# ART-Pi_LCD_Camera.net
KiCad netlist of a schematic drawn in Altium Designer
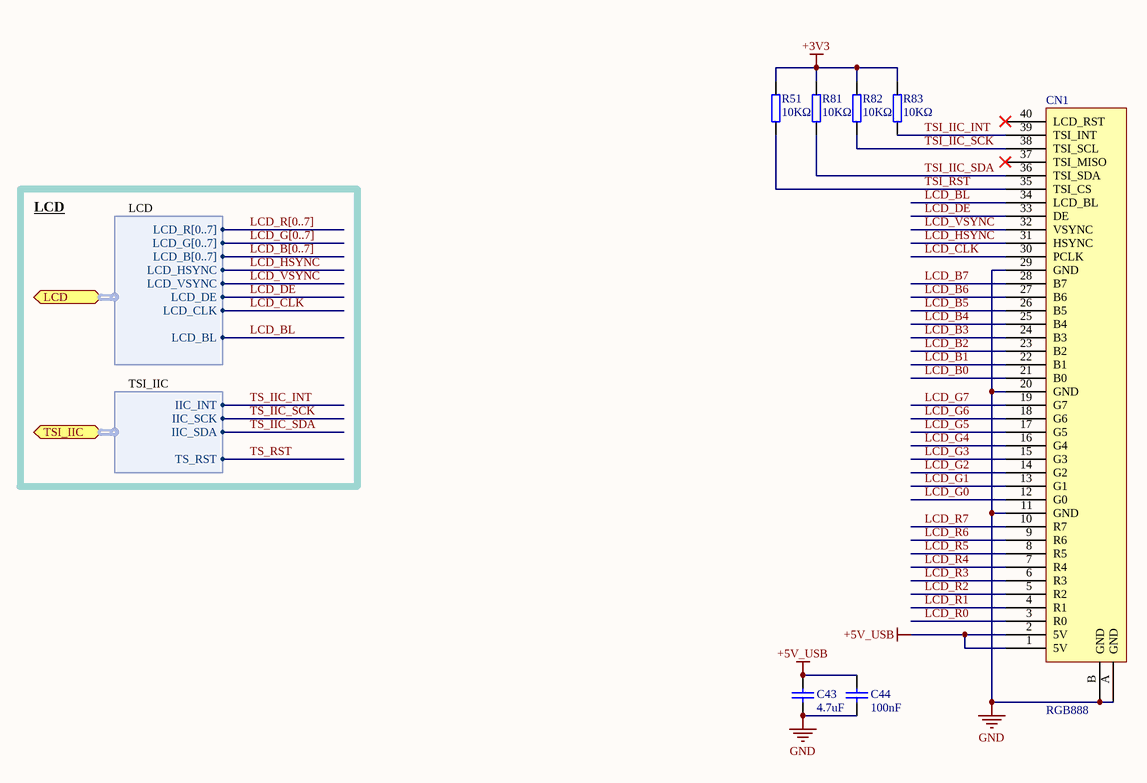
[diagram p0: ART-Pi_LCD&Camera.SchDoc]

(export (version "E")
  (design (tool "Eeschema 10.0.6"))
  (components
    (comp (ref "C43")
      (value "4.7uF")
      (footprint "0402_C")
      (description "Capacitor")
      (fields (field (name "PUBLISHER") "Altium Limited"))
      (libsource (lib "ART-Pi_STM32H750_COPY") (part "Cap"))
    )
    (comp (ref "C44")
      (value "100nF")
      (footprint "0402_C")
      (description "Capacitor")
      (fields (field (name "PUBLISHER") "Altium Limited"))
      (libsource (lib "ART-Pi_STM32H750_COPY") (part "Cap"))
    )
    (comp (ref "CN1")
      (value "RGB888")
      (footprint "FPC-TOP40")
      (description "FPC-40P-0.5mm")
      (libsource (lib "ART-Pi_STM32H750_COPY") (part "FPC-40"))
    )
    (comp (ref "R51")
      (value "10KΩ")
      (footprint "0402_R")
      (description "Resister")
      (libsource (lib "ART-Pi_STM32H750_COPY") (part "Res"))
    )
    (comp (ref "R81")
      (value "10KΩ")
      (footprint "0402_R")
      (description "Resister")
      (libsource (lib "ART-Pi_STM32H750_COPY") (part "Res"))
    )
    (comp (ref "R82")
      (value "10KΩ")
      (footprint "0402_R")
      (description "Resister")
      (libsource (lib "ART-Pi_STM32H750_COPY") (part "Res"))
    )
    (comp (ref "R83")
      (value "10KΩ")
      (footprint "0402_R")
      (description "Resister")
      (libsource (lib "ART-Pi_STM32H750_COPY") (part "Res"))
    )
  )
  (nets
    (net (code "2") (name "+3V3") (class "Default")
      (node (ref "R51") (pin "1") (pinfunction "1_1") (pintype "passive"))
      (node (ref "R81") (pin "1") (pinfunction "1_1") (pintype "passive"))
      (node (ref "R82") (pin "1") (pinfunction "1_1") (pintype "passive"))
      (node (ref "R83") (pin "1") (pinfunction "1_1") (pintype "passive"))
    )
    (net (code "3") (name "+5V_USB") (class "Default")
      (node (ref "C43") (pin "2") (pinfunction "2_2") (pintype "passive"))
      (node (ref "C44") (pin "2") (pinfunction "2_2") (pintype "passive"))
      (node (ref "CN1") (pin "1") (pinfunction "5V_1") (pintype "passive"))
      (node (ref "CN1") (pin "2") (pinfunction "5V_2") (pintype "passive"))
    )
    (net (code "4") (name "/LCD_B0") (class "Default")
      (node (ref "CN1") (pin "21") (pinfunction "B0_21") (pintype "passive"))
    )
    (net (code "5") (name "/LCD_B1") (class "Default")
      (node (ref "CN1") (pin "22") (pinfunction "B1_22") (pintype "passive"))
    )
    (net (code "6") (name "/LCD_B2") (class "Default")
      (node (ref "CN1") (pin "23") (pinfunction "B2_23") (pintype "passive"))
    )
    (net (code "7") (name "/LCD_B3") (class "Default")
      (node (ref "CN1") (pin "24") (pinfunction "B3_24") (pintype "passive"))
    )
    (net (code "8") (name "/LCD_B4") (class "Default")
      (node (ref "CN1") (pin "25") (pinfunction "B4_25") (pintype "passive"))
    )
    (net (code "9") (name "/LCD_B5") (class "Default")
      (node (ref "CN1") (pin "26") (pinfunction "B5_26") (pintype "passive"))
    )
    (net (code "10") (name "/LCD_B6") (class "Default")
      (node (ref "CN1") (pin "27") (pinfunction "B6_27") (pintype "passive"))
    )
    (net (code "11") (name "/LCD_B7") (class "Default")
      (node (ref "CN1") (pin "28") (pinfunction "B7_28") (pintype "passive"))
    )
    (net (code "12") (name "/LCD_BL") (class "Default")
      (node (ref "CN1") (pin "34") (pinfunction "LCD_BL_34") (pintype "passive"))
    )
    (net (code "14") (name "/LCD_CLK") (class "Default")
      (node (ref "CN1") (pin "30") (pinfunction "PCLK_30") (pintype "passive"))
    )
    (net (code "15") (name "/LCD_DE") (class "Default")
      (node (ref "CN1") (pin "33") (pinfunction "DE_33") (pintype "passive"))
    )
    (net (code "16") (name "/LCD_G0") (class "Default")
      (node (ref "CN1") (pin "12") (pinfunction "G0_12") (pintype "passive"))
    )
    (net (code "17") (name "/LCD_G1") (class "Default")
      (node (ref "CN1") (pin "13") (pinfunction "G1_13") (pintype "passive"))
    )
    (net (code "18") (name "/LCD_G2") (class "Default")
      (node (ref "CN1") (pin "14") (pinfunction "G2_14") (pintype "passive"))
    )
    (net (code "19") (name "/LCD_G3") (class "Default")
      (node (ref "CN1") (pin "15") (pinfunction "G3_15") (pintype "passive"))
    )
    (net (code "20") (name "/LCD_G4") (class "Default")
      (node (ref "CN1") (pin "16") (pinfunction "G4_16") (pintype "passive"))
    )
    (net (code "21") (name "/LCD_G5") (class "Default")
      (node (ref "CN1") (pin "17") (pinfunction "G5_17") (pintype "passive"))
    )
    (net (code "22") (name "/LCD_G6") (class "Default")
      (node (ref "CN1") (pin "18") (pinfunction "G6_18") (pintype "passive"))
    )
    (net (code "23") (name "/LCD_G7") (class "Default")
      (node (ref "CN1") (pin "19") (pinfunction "G7_19") (pintype "passive"))
    )
    (net (code "25") (name "/LCD_HSYNC") (class "Default")
      (node (ref "CN1") (pin "31") (pinfunction "HSYNC_31") (pintype "passive"))
    )
    (net (code "26") (name "/LCD_R0") (class "Default")
      (node (ref "CN1") (pin "3") (pinfunction "R0_3") (pintype "passive"))
    )
    (net (code "27") (name "/LCD_R1") (class "Default")
      (node (ref "CN1") (pin "4") (pinfunction "R1_4") (pintype "passive"))
    )
    (net (code "28") (name "/LCD_R2") (class "Default")
      (node (ref "CN1") (pin "5") (pinfunction "R2_5") (pintype "passive"))
    )
    (net (code "29") (name "/LCD_R3") (class "Default")
      (node (ref "CN1") (pin "6") (pinfunction "R3_6") (pintype "passive"))
    )
    (net (code "30") (name "/LCD_R4") (class "Default")
      (node (ref "CN1") (pin "7") (pinfunction "R4_7") (pintype "passive"))
    )
    (net (code "31") (name "/LCD_R5") (class "Default")
      (node (ref "CN1") (pin "8") (pinfunction "R5_8") (pintype "passive"))
    )
    (net (code "32") (name "/LCD_R6") (class "Default")
      (node (ref "CN1") (pin "9") (pinfunction "R6_9") (pintype "passive"))
    )
    (net (code "33") (name "/LCD_R7") (class "Default")
      (node (ref "CN1") (pin "10") (pinfunction "R7_10") (pintype "passive"))
    )
    (net (code "35") (name "/LCD_VSYNC") (class "Default")
      (node (ref "CN1") (pin "32") (pinfunction "VSYNC_32") (pintype "passive"))
    )
    (net (code "36") (name "/TSI_IIC_INT") (class "Default")
      (node (ref "CN1") (pin "39") (pinfunction "TSI_INT_39") (pintype "passive"))
      (node (ref "R83") (pin "2") (pinfunction "2_2") (pintype "passive"))
    )
    (net (code "37") (name "/TSI_IIC_SCK") (class "Default")
      (node (ref "CN1") (pin "38") (pinfunction "TSI_SCL_38") (pintype "passive"))
      (node (ref "R82") (pin "2") (pinfunction "2_2") (pintype "passive"))
    )
    (net (code "38") (name "/TSI_IIC_SDA") (class "Default")
      (node (ref "CN1") (pin "36") (pinfunction "TSI_SDA_36") (pintype "passive"))
      (node (ref "R81") (pin "2") (pinfunction "2_2") (pintype "passive"))
    )
    (net (code "39") (name "/TSI_RST") (class "Default")
      (node (ref "CN1") (pin "35") (pinfunction "TSI_CS_35") (pintype "passive"))
      (node (ref "R51") (pin "2") (pinfunction "2_2") (pintype "passive"))
    )
    (net (code "45") (name "GND") (class "Default")
      (node (ref "C43") (pin "1") (pinfunction "1_1") (pintype "passive"))
      (node (ref "C44") (pin "1") (pinfunction "1_1") (pintype "passive"))
      (node (ref "CN1") (pin "11") (pinfunction "GND_11") (pintype "passive"))
      (node (ref "CN1") (pin "20") (pinfunction "GND_20") (pintype "passive"))
      (node (ref "CN1") (pin "29") (pinfunction "GND_29") (pintype "passive"))
      (node (ref "CN1") (pin "A") (pinfunction "GND_A") (pintype "passive"))
      (node (ref "CN1") (pin "B") (pinfunction "GND_B") (pintype "passive"))
    )
    (net (code "46") (name "unconnected-(CN1-LCD_RST-Pad40)") (class "Default")
      (node (ref "CN1") (pin "40") (pinfunction "LCD_RST_40") (pintype "passive+no_connect"))
    )
    (net (code "47") (name "unconnected-(CN1-TSI_MISO-Pad37)") (class "Default")
      (node (ref "CN1") (pin "37") (pinfunction "TSI_MISO_37") (pintype "passive+no_connect"))
    )
  )
)
